# power.net
KiCad netlist of a schematic drawn in EAGLE
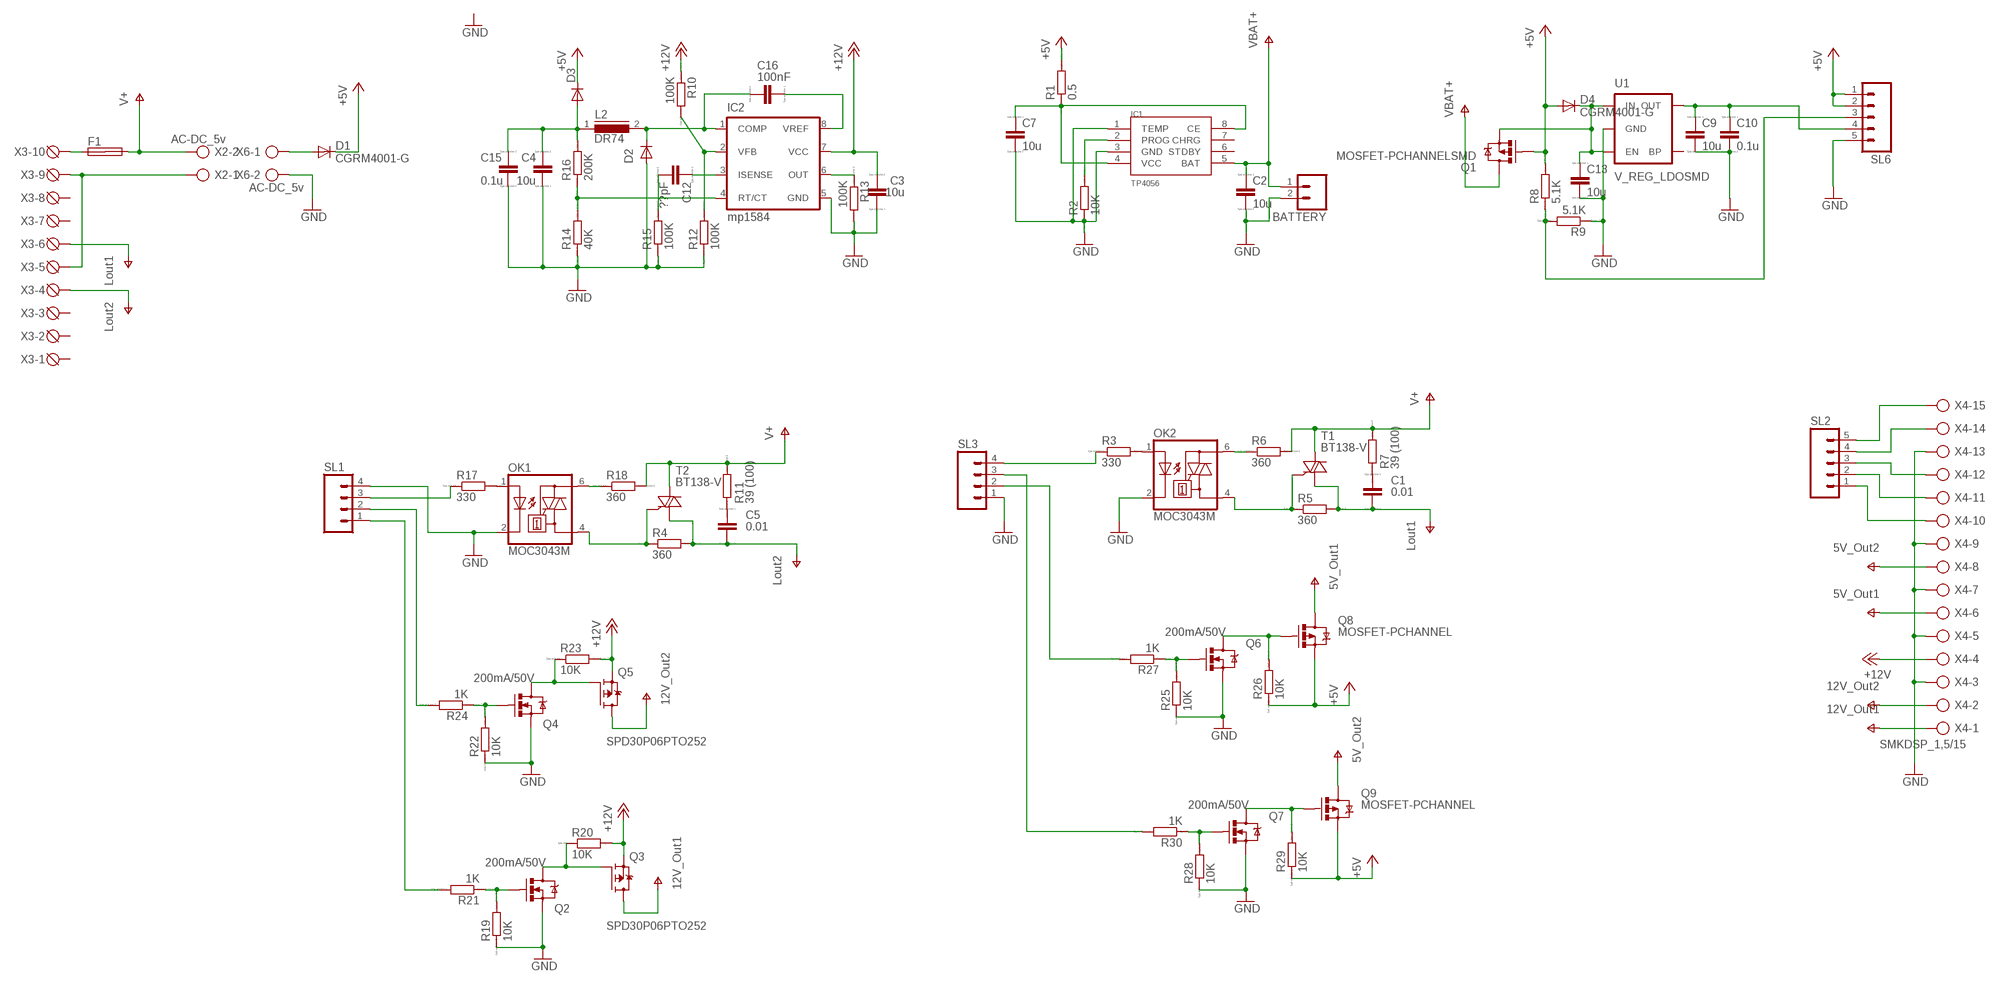
[diagram p0: schematic, sheet 1]

(export (version "E")
  (design (tool "Eeschema 10.0.6"))
  (components
    (comp (ref "BATTERY")
      (value "M02")
      (footprint "eagle-import:02P")
      (libsource (lib "eagle-import") (part "M02"))
    )
    (comp (ref "C1")
      (value "0.01")
      (footprint "eagle-import:C075-032X103")
      (libsource (lib "eagle-import") (part "C-EU075-032X103"))
    )
    (comp (ref "C2")
      (value "10u")
      (footprint "eagle-import:C0805")
      (libsource (lib "eagle-import") (part "C-EUC0805"))
    )
    (comp (ref "C3")
      (value "10u")
      (footprint "eagle-import:C1206")
      (libsource (lib "eagle-import") (part "C-EUC1206"))
    )
    (comp (ref "C4")
      (value "10u")
      (footprint "eagle-import:C1206")
      (libsource (lib "eagle-import") (part "C-EUC1206"))
    )
    (comp (ref "C5")
      (value "0.01")
      (footprint "eagle-import:C075-032X103")
      (libsource (lib "eagle-import") (part "C-EU075-032X103"))
    )
    (comp (ref "C7")
      (value "10u")
      (footprint "eagle-import:C0805")
      (libsource (lib "eagle-import") (part "C-EUC0805"))
    )
    (comp (ref "C9")
      (value "10u")
      (footprint "eagle-import:C0805")
      (libsource (lib "eagle-import") (part "C-EUC0805"))
    )
    (comp (ref "C10")
      (value "0.1u")
      (footprint "eagle-import:C0805")
      (libsource (lib "eagle-import") (part "C-EUC0805"))
    )
    (comp (ref "C12")
      (value "??pF")
      (footprint "eagle-import:C0603")
      (libsource (lib "eagle-import") (part "C-EUC0603"))
    )
    (comp (ref "C13")
      (value "10u")
      (footprint "eagle-import:C0805")
      (libsource (lib "eagle-import") (part "C-EUC0805"))
    )
    (comp (ref "C15")
      (value "0.1u")
      (footprint "eagle-import:C0805")
      (libsource (lib "eagle-import") (part "C-EUC0805"))
    )
    (comp (ref "C16")
      (value "100nF")
      (footprint "eagle-import:C0603")
      (libsource (lib "eagle-import") (part "C-EUC0603"))
    )
    (comp (ref "D1")
      (value "CGRM4001-G")
      (footprint "eagle-import:SOD-123_MINI-SMA")
      (libsource (lib "eagle-import") (part "CGRM400-G1"))
    )
    (comp (ref "D2")
      (value "ES2D")
      (footprint "eagle-import:SMB")
      (libsource (lib "eagle-import") (part "ES2D"))
    )
    (comp (ref "D3")
      (value "CGRM4001-G")
      (footprint "eagle-import:SOD-123_MINI-SMA")
      (libsource (lib "eagle-import") (part "CGRM400-G1"))
    )
    (comp (ref "D4")
      (value "CGRM4001-G")
      (footprint "eagle-import:SOD-123_MINI-SMA")
      (libsource (lib "eagle-import") (part "CGRM400-G1"))
    )
    (comp (ref "F1")
      (value "SHK20L")
      (footprint "eagle-import:SHK20L")
      (libsource (lib "eagle-import") (part "SHK20L"))
    )
    (comp (ref "IC1")
      (value "TP4056")
      (footprint "eagle-import:SOP-8")
      (libsource (lib "eagle-import") (part "TP4056"))
    )
    (comp (ref "IC2")
      (value "mp1584")
      (footprint "eagle-import:SO-08")
      (libsource (lib "eagle-import") (part "UC384D14"))
    )
    (comp (ref "L2")
      (value "DR74")
      (footprint "eagle-import:DR74")
      (libsource (lib "eagle-import") (part "DR74"))
    )
    (comp (ref "OK1")
      (value "MOC3043M")
      (footprint "eagle-import:DIL06")
      (fields (field (name "MF") "FAIRCHILD SEMICONDUCTOR") (field (name "MPN") "MOC3043-M"))
      (libsource (lib "eagle-import") (part "MOC3043M"))
    )
    (comp (ref "OK2")
      (value "MOC3043M")
      (footprint "eagle-import:DIL06")
      (fields (field (name "MF") "FAIRCHILD SEMICONDUCTOR") (field (name "MPN") "MOC3043-M"))
      (libsource (lib "eagle-import") (part "MOC3043M"))
    )
    (comp (ref "Q1")
      (value "MOSFET-PCHANNELSMD")
      (footprint "eagle-import:SOT23-3")
      (libsource (lib "eagle-import") (part "MOSFET-PCHANNELSMD"))
    )
    (comp (ref "Q2")
      (value "200mA/50V")
      (footprint "eagle-import:SOT23-3")
      (libsource (lib "eagle-import") (part "MOSFET-NCHANNELBSS138"))
    )
    (comp (ref "Q3")
      (value "SPD30P06PTO252")
      (footprint "eagle-import:TO252")
      (libsource (lib "eagle-import") (part "SPD30P06PTO252"))
    )
    (comp (ref "Q4")
      (value "200mA/50V")
      (footprint "eagle-import:SOT23-3")
      (libsource (lib "eagle-import") (part "MOSFET-NCHANNELBSS138"))
    )
    (comp (ref "Q5")
      (value "SPD30P06PTO252")
      (footprint "eagle-import:TO252")
      (libsource (lib "eagle-import") (part "SPD30P06PTO252"))
    )
    (comp (ref "Q6")
      (value "200mA/50V")
      (footprint "eagle-import:SOT23-3")
      (libsource (lib "eagle-import") (part "MOSFET-NCHANNELBSS138"))
    )
    (comp (ref "Q7")
      (value "200mA/50V")
      (footprint "eagle-import:SOT23-3")
      (libsource (lib "eagle-import") (part "MOSFET-NCHANNELBSS138"))
    )
    (comp (ref "Q8")
      (value "MOSFET-PCHANNEL")
      (footprint "eagle-import:SOT23-3")
      (libsource (lib "eagle-import") (part "MOSFET-PCHANNEL"))
    )
    (comp (ref "Q9")
      (value "MOSFET-PCHANNEL")
      (footprint "eagle-import:SOT23-3")
      (libsource (lib "eagle-import") (part "MOSFET-PCHANNEL"))
    )
    (comp (ref "R1")
      (value "0.5")
      (footprint "eagle-import:R0805")
      (libsource (lib "eagle-import") (part "R-EU_R0805"))
    )
    (comp (ref "R2")
      (value "10K")
      (footprint "eagle-import:R0805")
      (libsource (lib "eagle-import") (part "R-EU_R0805"))
    )
    (comp (ref "R3")
      (value "330")
      (footprint "eagle-import:R1206")
      (libsource (lib "eagle-import") (part "R-EU_R1206"))
    )
    (comp (ref "R4")
      (value "360")
      (footprint "eagle-import:0204_7")
      (libsource (lib "eagle-import") (part "R-EU_0204_7"))
    )
    (comp (ref "R5")
      (value "360")
      (footprint "eagle-import:0204_7")
      (libsource (lib "eagle-import") (part "R-EU_0204_7"))
    )
    (comp (ref "R6")
      (value "360")
      (footprint "eagle-import:R1206")
      (libsource (lib "eagle-import") (part "R-EU_R1206"))
    )
    (comp (ref "R7")
      (value "39 (100)")
      (footprint "eagle-import:0411_12")
      (libsource (lib "eagle-import") (part "R-EU_0411_12"))
    )
    (comp (ref "R8")
      (value "5.1K")
      (footprint "eagle-import:R0805")
      (libsource (lib "eagle-import") (part "R-EU_R0805"))
    )
    (comp (ref "R9")
      (value "5.1K")
      (footprint "eagle-import:R0805")
      (libsource (lib "eagle-import") (part "R-EU_R0805"))
    )
    (comp (ref "R10")
      (value "100K")
      (footprint "eagle-import:R0603")
      (libsource (lib "eagle-import") (part "R-EU_R0603"))
    )
    (comp (ref "R11")
      (value "39 (100)")
      (footprint "eagle-import:0411_12")
      (libsource (lib "eagle-import") (part "R-EU_0411_12"))
    )
    (comp (ref "R12")
      (value "100K")
      (footprint "eagle-import:R0603")
      (libsource (lib "eagle-import") (part "R-EU_R0603"))
    )
    (comp (ref "R13")
      (value "100K")
      (footprint "eagle-import:R0603")
      (libsource (lib "eagle-import") (part "R-EU_R0603"))
    )
    (comp (ref "R14")
      (value "40K")
      (footprint "eagle-import:R0603")
      (libsource (lib "eagle-import") (part "R-EU_R0603"))
    )
    (comp (ref "R15")
      (value "100K")
      (footprint "eagle-import:R0603")
      (libsource (lib "eagle-import") (part "R-EU_R0603"))
    )
    (comp (ref "R16")
      (value "200K")
      (footprint "eagle-import:R0603")
      (libsource (lib "eagle-import") (part "R-EU_R0603"))
    )
    (comp (ref "R17")
      (value "330")
      (footprint "eagle-import:R1206")
      (libsource (lib "eagle-import") (part "R-EU_R1206"))
    )
    (comp (ref "R18")
      (value "360")
      (footprint "eagle-import:R1206")
      (libsource (lib "eagle-import") (part "R-EU_R1206"))
    )
    (comp (ref "R19")
      (value "10K")
      (footprint "eagle-import:R0805")
      (libsource (lib "eagle-import") (part "R-EU_R0805"))
    )
    (comp (ref "R20")
      (value "10K")
      (footprint "eagle-import:R0805")
      (libsource (lib "eagle-import") (part "R-EU_R0805"))
    )
    (comp (ref "R21")
      (value "1K")
      (footprint "eagle-import:R0805")
      (libsource (lib "eagle-import") (part "R-EU_R0805"))
    )
    (comp (ref "R22")
      (value "10K")
      (footprint "eagle-import:R0805")
      (libsource (lib "eagle-import") (part "R-EU_R0805"))
    )
    (comp (ref "R23")
      (value "10K")
      (footprint "eagle-import:R0805")
      (libsource (lib "eagle-import") (part "R-EU_R0805"))
    )
    (comp (ref "R24")
      (value "1K")
      (footprint "eagle-import:R0805")
      (libsource (lib "eagle-import") (part "R-EU_R0805"))
    )
    (comp (ref "R25")
      (value "10K")
      (footprint "eagle-import:R0805")
      (libsource (lib "eagle-import") (part "R-EU_R0805"))
    )
    (comp (ref "R26")
      (value "10K")
      (footprint "eagle-import:R0805")
      (libsource (lib "eagle-import") (part "R-EU_R0805"))
    )
    (comp (ref "R27")
      (value "1K")
      (footprint "eagle-import:R0805")
      (libsource (lib "eagle-import") (part "R-EU_R0805"))
    )
    (comp (ref "R28")
      (value "10K")
      (footprint "eagle-import:R0805")
      (libsource (lib "eagle-import") (part "R-EU_R0805"))
    )
    (comp (ref "R29")
      (value "10K")
      (footprint "eagle-import:R0805")
      (libsource (lib "eagle-import") (part "R-EU_R0805"))
    )
    (comp (ref "R30")
      (value "1K")
      (footprint "eagle-import:R0805")
      (libsource (lib "eagle-import") (part "R-EU_R0805"))
    )
    (comp (ref "SL1")
      (value "M04")
      (footprint "eagle-import:04P")
      (libsource (lib "eagle-import") (part "M04"))
    )
    (comp (ref "SL2")
      (value "M05")
      (footprint "eagle-import:05P")
      (libsource (lib "eagle-import") (part "M05"))
    )
    (comp (ref "SL3")
      (value "M04")
      (footprint "eagle-import:04P")
      (libsource (lib "eagle-import") (part "M04"))
    )
    (comp (ref "SL6")
      (value "M05")
      (footprint "eagle-import:05P")
      (libsource (lib "eagle-import") (part "M05"))
    )
    (comp (ref "T1")
      (value "BT138-V")
      (footprint "eagle-import:TO220BV")
      (libsource (lib "eagle-import") (part "BT138-V"))
    )
    (comp (ref "T2")
      (value "BT138-V")
      (footprint "eagle-import:TO220BV")
      (libsource (lib "eagle-import") (part "BT138-V"))
    )
    (comp (ref "U1")
      (value "V_REG_LDOSMD")
      (footprint "eagle-import:SOT23-5")
      (libsource (lib "eagle-import") (part "V_REG_LDOSMD"))
    )
    (comp (ref "X2")
      (value "AC-DC_5v")
      (footprint "eagle-import:AK300_2")
      (libsource (lib "eagle-import") (part "AK300/2"))
    )
    (comp (ref "X3")
      (value "DG3XX-10")
      (footprint "eagle-import:DG129-7.5-10P")
      (libsource (lib "eagle-import") (part "DG3XX-10"))
    )
    (comp (ref "X4")
      (value "SMKDSP_1,5/15")
      (footprint "eagle-import:SMKDSP_1,5_15")
      (libsource (lib "eagle-import") (part "SMKDSP_1,5/15"))
    )
    (comp (ref "X6")
      (value "AC-DC_5v")
      (footprint "eagle-import:AK300_2")
      (libsource (lib "eagle-import") (part "AK300/2"))
    )
  )
  (nets
    (net (code "1") (name "+5V") (class "Default")
      (node (ref "D1") (pin "C") (pinfunction "C_C") (pintype "passive"))
      (node (ref "D3") (pin "C") (pinfunction "C_C") (pintype "passive"))
      (node (ref "D4") (pin "A") (pinfunction "A_A") (pintype "passive"))
      (node (ref "Q1") (pin "1") (pinfunction "G_1") (pintype "passive"))
      (node (ref "Q8") (pin "2") (pinfunction "S_2") (pintype "passive"))
      (node (ref "Q9") (pin "2") (pinfunction "S_2") (pintype "passive"))
      (node (ref "R1") (pin "2") (pinfunction "2_2") (pintype "passive"))
      (node (ref "R26") (pin "1") (pinfunction "1_1") (pintype "passive"))
      (node (ref "R29") (pin "1") (pinfunction "1_1") (pintype "passive"))
      (node (ref "R8") (pin "2") (pinfunction "2_2") (pintype "passive"))
      (node (ref "SL6") (pin "1") (pinfunction "1_1") (pintype "passive"))
      (node (ref "SL6") (pin "2") (pinfunction "2_2") (pintype "passive"))
    )
    (net (code "2") (name "+12V") (class "Default")
      (node (ref "C3") (pin "2") (pinfunction "2_2") (pintype "passive"))
      (node (ref "IC2") (pin "7") (pinfunction "VCC_7") (pintype "power_in"))
      (node (ref "Q3") (pin "2") (pinfunction "S_2") (pintype "passive"))
      (node (ref "Q5") (pin "2") (pinfunction "S_2") (pintype "passive"))
      (node (ref "R10") (pin "1") (pinfunction "1_1") (pintype "passive"))
      (node (ref "R20") (pin "2") (pinfunction "2_2") (pintype "passive"))
      (node (ref "R23") (pin "2") (pinfunction "2_2") (pintype "passive"))
      (node (ref "X4") (pin "4") (pinfunction "KL_4") (pintype "passive"))
    )
    (net (code "3") (name "5V_Out1") (class "Default")
      (node (ref "Q8") (pin "3") (pinfunction "D_3") (pintype "passive"))
      (node (ref "X4") (pin "6") (pinfunction "KL_6") (pintype "passive"))
    )
    (net (code "4") (name "5V_Out2") (class "Default")
      (node (ref "Q9") (pin "3") (pinfunction "D_3") (pintype "passive"))
      (node (ref "X4") (pin "8") (pinfunction "KL_8") (pintype "passive"))
    )
    (net (code "5") (name "12V_Out1") (class "Default")
      (node (ref "Q3") (pin "3") (pinfunction "D_3") (pintype "passive"))
      (node (ref "X4") (pin "1") (pinfunction "KL_1") (pintype "passive"))
    )
    (net (code "6") (name "12V_Out2") (class "Default")
      (node (ref "Q5") (pin "3") (pinfunction "D_3") (pintype "passive"))
      (node (ref "X4") (pin "2") (pinfunction "KL_2") (pintype "passive"))
    )
    (net (code "7") (name "GND") (class "Default")
      (node (ref "BATTERY") (pin "2") (pinfunction "2_2") (pintype "passive"))
      (node (ref "C10") (pin "2") (pinfunction "2_2") (pintype "passive"))
      (node (ref "C13") (pin "2") (pinfunction "2_2") (pintype "passive"))
      (node (ref "C15") (pin "2") (pinfunction "2_2") (pintype "passive"))
      (node (ref "C2") (pin "2") (pinfunction "2_2") (pintype "passive"))
      (node (ref "C3") (pin "1") (pinfunction "1_1") (pintype "passive"))
      (node (ref "C4") (pin "1") (pinfunction "1_1") (pintype "passive"))
      (node (ref "C7") (pin "2") (pinfunction "2_2") (pintype "passive"))
      (node (ref "C9") (pin "2") (pinfunction "2_2") (pintype "passive"))
      (node (ref "D2") (pin "A") (pinfunction "A_A") (pintype "passive"))
      (node (ref "IC1") (pin "1") (pinfunction "TEMP_1") (pintype "bidirectional"))
      (node (ref "IC1") (pin "3") (pinfunction "GND_3") (pintype "bidirectional"))
      (node (ref "IC2") (pin "5") (pinfunction "GND_5") (pintype "power_in"))
      (node (ref "OK1") (pin "2") (pinfunction "C_2") (pintype "passive"))
      (node (ref "OK2") (pin "2") (pinfunction "C_2") (pintype "passive"))
      (node (ref "Q2") (pin "2") (pinfunction "S_2") (pintype "passive"))
      (node (ref "Q4") (pin "2") (pinfunction "S_2") (pintype "passive"))
      (node (ref "Q6") (pin "2") (pinfunction "S_2") (pintype "passive"))
      (node (ref "Q7") (pin "2") (pinfunction "S_2") (pintype "passive"))
      (node (ref "R12") (pin "1") (pinfunction "1_1") (pintype "passive"))
      (node (ref "R13") (pin "2") (pinfunction "2_2") (pintype "passive"))
      (node (ref "R14") (pin "1") (pinfunction "1_1") (pintype "passive"))
      (node (ref "R15") (pin "1") (pinfunction "1_1") (pintype "passive"))
      (node (ref "R19") (pin "1") (pinfunction "1_1") (pintype "passive"))
      (node (ref "R2") (pin "1") (pinfunction "1_1") (pintype "passive"))
      (node (ref "R22") (pin "1") (pinfunction "1_1") (pintype "passive"))
      (node (ref "R25") (pin "1") (pinfunction "1_1") (pintype "passive"))
      (node (ref "R28") (pin "1") (pinfunction "1_1") (pintype "passive"))
      (node (ref "R9") (pin "1") (pinfunction "1_1") (pintype "passive"))
      (node (ref "SL1") (pin "4") (pinfunction "4_4") (pintype "passive"))
      (node (ref "SL3") (pin "1") (pinfunction "1_1") (pintype "passive"))
      (node (ref "SL6") (pin "5") (pinfunction "5_5") (pintype "passive"))
      (node (ref "U1") (pin "2") (pinfunction "GND_2") (pintype "input"))
      (node (ref "X4") (pin "13") (pinfunction "KL_13") (pintype "passive"))
      (node (ref "X4") (pin "3") (pinfunction "KL_3") (pintype "passive"))
      (node (ref "X4") (pin "5") (pinfunction "KL_5") (pintype "passive"))
      (node (ref "X4") (pin "7") (pinfunction "KL_7") (pintype "passive"))
      (node (ref "X4") (pin "9") (pinfunction "KL_9") (pintype "passive"))
      (node (ref "X6") (pin "2") (pinfunction "KL_2") (pintype "passive"))
    )
    (net (code "8") (name "Lout1") (class "Default")
      (node (ref "C1") (pin "2") (pinfunction "2_2") (pintype "passive"))
      (node (ref "R5") (pin "2") (pinfunction "2_2") (pintype "passive"))
      (node (ref "T1") (pin "T1") (pinfunction "A1_T1") (pintype "passive"))
      (node (ref "X3") (pin "6") (pinfunction "KL_6") (pintype "passive"))
    )
    (net (code "9") (name "Lout2") (class "Default")
      (node (ref "C5") (pin "2") (pinfunction "2_2") (pintype "passive"))
      (node (ref "R4") (pin "2") (pinfunction "2_2") (pintype "passive"))
      (node (ref "T2") (pin "T1") (pinfunction "A1_T1") (pintype "passive"))
      (node (ref "X3") (pin "4") (pinfunction "KL_4") (pintype "passive"))
    )
    (net (code "10") (name "Net-(C1-Pad1)") (class "Default")
      (node (ref "C1") (pin "1") (pinfunction "1_1") (pintype "passive"))
      (node (ref "R7") (pin "1") (pinfunction "1_1") (pintype "passive"))
    )
    (net (code "11") (name "Net-(C5-Pad1)") (class "Default")
      (node (ref "C5") (pin "1") (pinfunction "1_1") (pintype "passive"))
      (node (ref "R11") (pin "1") (pinfunction "1_1") (pintype "passive"))
    )
    (net (code "12") (name "Net-(C12-Pad2)") (class "Default")
      (node (ref "C12") (pin "2") (pinfunction "2_2") (pintype "passive"))
      (node (ref "R15") (pin "2") (pinfunction "2_2") (pintype "passive"))
    )
    (net (code "13") (name "Net-(C15-Pad1)") (class "Default")
      (node (ref "C15") (pin "1") (pinfunction "1_1") (pintype "passive"))
      (node (ref "C4") (pin "2") (pinfunction "2_2") (pintype "passive"))
      (node (ref "D3") (pin "A") (pinfunction "A_A") (pintype "passive"))
      (node (ref "L2") (pin "1") (pinfunction "1_1") (pintype "passive"))
      (node (ref "R16") (pin "2") (pinfunction "2_2") (pintype "passive"))
    )
    (net (code "14") (name "Net-(IC1-CE)") (class "Default")
      (node (ref "C7") (pin "1") (pinfunction "1_1") (pintype "passive"))
      (node (ref "IC1") (pin "4") (pinfunction "VCC_4") (pintype "bidirectional"))
      (node (ref "IC1") (pin "8") (pinfunction "CE_8") (pintype "bidirectional"))
      (node (ref "R1") (pin "1") (pinfunction "1_1") (pintype "passive"))
    )
    (net (code "15") (name "Net-(IC1-PROG)") (class "Default")
      (node (ref "IC1") (pin "2") (pinfunction "PROG_2") (pintype "bidirectional"))
      (node (ref "R2") (pin "2") (pinfunction "2_2") (pintype "passive"))
    )
    (net (code "16") (name "Net-(IC2-COMP)") (class "Default")
      (node (ref "C16") (pin "2") (pinfunction "2_2") (pintype "passive"))
      (node (ref "D2") (pin "C") (pinfunction "C_C") (pintype "passive"))
      (node (ref "IC2") (pin "1") (pinfunction "COMP_1") (pintype "passive"))
      (node (ref "L2") (pin "2") (pinfunction "2_2") (pintype "passive"))
    )
    (net (code "17") (name "Net-(IC2-ISENSE)") (class "Default")
      (node (ref "C12") (pin "1") (pinfunction "1_1") (pintype "passive"))
      (node (ref "IC2") (pin "3") (pinfunction "ISENSE_3") (pintype "input"))
    )
    (net (code "18") (name "Net-(IC2-OUT)") (class "Default")
      (node (ref "IC2") (pin "6") (pinfunction "OUT_6") (pintype "output"))
      (node (ref "R13") (pin "1") (pinfunction "1_1") (pintype "passive"))
    )
    (net (code "19") (name "Net-(IC2-RT{slash}CT)") (class "Default")
      (node (ref "IC2") (pin "4") (pinfunction "RT/CT_4") (pintype "passive"))
      (node (ref "R14") (pin "2") (pinfunction "2_2") (pintype "passive"))
      (node (ref "R16") (pin "1") (pinfunction "1_1") (pintype "passive"))
    )
    (net (code "20") (name "Net-(IC2-VFB)") (class "Default")
      (node (ref "IC2") (pin "2") (pinfunction "VFB_2") (pintype "input"))
      (node (ref "R10") (pin "2") (pinfunction "2_2") (pintype "passive"))
      (node (ref "R12") (pin "2") (pinfunction "2_2") (pintype "passive"))
    )
    (net (code "21") (name "Net-(IC2-VREF)") (class "Default")
      (node (ref "C16") (pin "1") (pinfunction "1_1") (pintype "passive"))
      (node (ref "IC2") (pin "8") (pinfunction "VREF_8") (pintype "passive"))
    )
    (net (code "22") (name "Net-(OK1-A)") (class "Default")
      (node (ref "OK1") (pin "1") (pinfunction "A_1") (pintype "passive"))
      (node (ref "R17") (pin "2") (pinfunction "2_2") (pintype "passive"))
    )
    (net (code "23") (name "Net-(OK1-A1)") (class "Default")
      (node (ref "OK1") (pin "4") (pinfunction "A1_4") (pintype "passive"))
      (node (ref "R4") (pin "1") (pinfunction "1_1") (pintype "passive"))
      (node (ref "T2") (pin "G") (pinfunction "G_G") (pintype "passive"))
    )
    (net (code "24") (name "Net-(OK1-A2)") (class "Default")
      (node (ref "OK1") (pin "6") (pinfunction "A2_6") (pintype "passive"))
      (node (ref "R18") (pin "1") (pinfunction "1_1") (pintype "passive"))
    )
    (net (code "25") (name "Net-(OK2-A)") (class "Default")
      (node (ref "OK2") (pin "1") (pinfunction "A_1") (pintype "passive"))
      (node (ref "R3") (pin "2") (pinfunction "2_2") (pintype "passive"))
    )
    (net (code "26") (name "Net-(OK2-A1)") (class "Default")
      (node (ref "OK2") (pin "4") (pinfunction "A1_4") (pintype "passive"))
      (node (ref "R5") (pin "1") (pinfunction "1_1") (pintype "passive"))
      (node (ref "T1") (pin "G") (pinfunction "G_G") (pintype "passive"))
    )
    (net (code "27") (name "Net-(OK2-A2)") (class "Default")
      (node (ref "OK2") (pin "6") (pinfunction "A2_6") (pintype "passive"))
      (node (ref "R6") (pin "1") (pinfunction "1_1") (pintype "passive"))
    )
    (net (code "28") (name "Net-(Q1-S)") (class "Default")
      (node (ref "C13") (pin "1") (pinfunction "1_1") (pintype "passive"))
      (node (ref "D4") (pin "C") (pinfunction "C_C") (pintype "passive"))
      (node (ref "Q1") (pin "2") (pinfunction "S_2") (pintype "passive"))
      (node (ref "U1") (pin "1") (pinfunction "IN_1") (pintype "input"))
      (node (ref "U1") (pin "3") (pinfunction "EN_3") (pintype "input"))
    )
    (net (code "29") (name "Net-(Q2-D)") (class "Default")
      (node (ref "Q2") (pin "3") (pinfunction "D_3") (pintype "passive"))
      (node (ref "Q3") (pin "1") (pinfunction "G_1") (pintype "passive"))
      (node (ref "R20") (pin "1") (pinfunction "1_1") (pintype "passive"))
    )
    (net (code "30") (name "Net-(Q2-G)") (class "Default")
      (node (ref "Q2") (pin "1") (pinfunction "G_1") (pintype "passive"))
      (node (ref "R19") (pin "2") (pinfunction "2_2") (pintype "passive"))
      (node (ref "R21") (pin "1") (pinfunction "1_1") (pintype "passive"))
    )
    (net (code "31") (name "Net-(Q4-D)") (class "Default")
      (node (ref "Q4") (pin "3") (pinfunction "D_3") (pintype "passive"))
      (node (ref "Q5") (pin "1") (pinfunction "G_1") (pintype "passive"))
      (node (ref "R23") (pin "1") (pinfunction "1_1") (pintype "passive"))
    )
    (net (code "32") (name "Net-(Q4-G)") (class "Default")
      (node (ref "Q4") (pin "1") (pinfunction "G_1") (pintype "passive"))
      (node (ref "R22") (pin "2") (pinfunction "2_2") (pintype "passive"))
      (node (ref "R24") (pin "1") (pinfunction "1_1") (pintype "passive"))
    )
    (net (code "33") (name "Net-(Q6-D)") (class "Default")
      (node (ref "Q6") (pin "3") (pinfunction "D_3") (pintype "passive"))
      (node (ref "Q8") (pin "1") (pinfunction "G_1") (pintype "passive"))
      (node (ref "R26") (pin "2") (pinfunction "2_2") (pintype "passive"))
    )
    (net (code "34") (name "Net-(Q6-G)") (class "Default")
      (node (ref "Q6") (pin "1") (pinfunction "G_1") (pintype "passive"))
      (node (ref "R25") (pin "2") (pinfunction "2_2") (pintype "passive"))
      (node (ref "R27") (pin "1") (pinfunction "1_1") (pintype "passive"))
    )
    (net (code "35") (name "Net-(Q7-D)") (class "Default")
      (node (ref "Q7") (pin "3") (pinfunction "D_3") (pintype "passive"))
      (node (ref "Q9") (pin "1") (pinfunction "G_1") (pintype "passive"))
      (node (ref "R29") (pin "2") (pinfunction "2_2") (pintype "passive"))
    )
    (net (code "36") (name "Net-(Q7-G)") (class "Default")
      (node (ref "Q7") (pin "1") (pinfunction "G_1") (pintype "passive"))
      (node (ref "R28") (pin "2") (pinfunction "2_2") (pintype "passive"))
      (node (ref "R30") (pin "1") (pinfunction "1_1") (pintype "passive"))
    )
    (net (code "37") (name "Net-(R3-Pad1)") (class "Default")
      (node (ref "R3") (pin "1") (pinfunction "1_1") (pintype "passive"))
      (node (ref "SL3") (pin "4") (pinfunction "4_4") (pintype "passive"))
    )
    (net (code "38") (name "Net-(R8-Pad1)") (class "Default")
      (node (ref "R8") (pin "1") (pinfunction "1_1") (pintype "passive"))
      (node (ref "R9") (pin "2") (pinfunction "2_2") (pintype "passive"))
      (node (ref "SL6") (pin "3") (pinfunction "3_3") (pintype "passive"))
    )
    (net (code "39") (name "Net-(R17-Pad1)") (class "Default")
      (node (ref "R17") (pin "1") (pinfunction "1_1") (pintype "passive"))
      (node (ref "SL1") (pin "3") (pinfunction "3_3") (pintype "passive"))
    )
    (net (code "40") (name "Net-(R21-Pad2)") (class "Default")
      (node (ref "R21") (pin "2") (pinfunction "2_2") (pintype "passive"))
      (node (ref "SL1") (pin "1") (pinfunction "1_1") (pintype "passive"))
    )
    (net (code "41") (name "Net-(R24-Pad2)") (class "Default")
      (node (ref "R24") (pin "2") (pinfunction "2_2") (pintype "passive"))
      (node (ref "SL1") (pin "2") (pinfunction "2_2") (pintype "passive"))
    )
    (net (code "42") (name "Net-(R27-Pad2)") (class "Default")
      (node (ref "R27") (pin "2") (pinfunction "2_2") (pintype "passive"))
      (node (ref "SL3") (pin "2") (pinfunction "2_2") (pintype "passive"))
    )
    (net (code "43") (name "Net-(R30-Pad2)") (class "Default")
      (node (ref "R30") (pin "2") (pinfunction "2_2") (pintype "passive"))
      (node (ref "SL3") (pin "3") (pinfunction "3_3") (pintype "passive"))
    )
    (net (code "44") (name "Net-(U1-OUT)") (class "Default")
      (node (ref "C10") (pin "1") (pinfunction "1_1") (pintype "passive"))
      (node (ref "C9") (pin "1") (pinfunction "1_1") (pintype "passive"))
      (node (ref "SL6") (pin "4") (pinfunction "4_4") (pintype "passive"))
      (node (ref "U1") (pin "5") (pinfunction "OUT_5") (pintype "passive"))
    )
    (net (code "45") (name "Net-(X2A-KL)") (class "Default")
      (node (ref "X2") (pin "1") (pinfunction "KL_1") (pintype "passive"))
      (node (ref "X3") (pin "5") (pinfunction "KL_5") (pintype "passive"))
      (node (ref "X3") (pin "9") (pinfunction "KL_9") (pintype "passive"))
    )
    (net (code "46") (name "Net-(X3B-KL)") (class "Default")
      (node (ref "F1") (pin "1A") (pinfunction "1A_1A") (pintype "passive"))
      (node (ref "X3") (pin "10") (pinfunction "KL_10") (pintype "passive"))
    )
    (net (code "47") (name "Net-(X4B-KL)") (class "Default")
      (node (ref "SL2") (pin "1") (pinfunction "1_1") (pintype "passive"))
      (node (ref "X4") (pin "10") (pinfunction "KL_10") (pintype "passive"))
    )
    (net (code "48") (name "Net-(X4C-KL)") (class "Default")
      (node (ref "SL2") (pin "2") (pinfunction "2_2") (pintype "passive"))
      (node (ref "X4") (pin "11") (pinfunction "KL_11") (pintype "passive"))
    )
    (net (code "49") (name "Net-(X4D-KL)") (class "Default")
      (node (ref "SL2") (pin "3") (pinfunction "3_3") (pintype "passive"))
      (node (ref "X4") (pin "12") (pinfunction "KL_12") (pintype "passive"))
    )
    (net (code "50") (name "Net-(X4F-KL)") (class "Default")
      (node (ref "SL2") (pin "4") (pinfunction "4_4") (pintype "passive"))
      (node (ref "X4") (pin "14") (pinfunction "KL_14") (pintype "passive"))
    )
    (net (code "51") (name "Net-(X4G-KL)") (class "Default")
      (node (ref "SL2") (pin "5") (pinfunction "5_5") (pintype "passive"))
      (node (ref "X4") (pin "15") (pinfunction "KL_15") (pintype "passive"))
    )
    (net (code "52") (name "Net-(X6A-KL)") (class "Default")
      (node (ref "D1") (pin "A") (pinfunction "A_A") (pintype "passive"))
      (node (ref "X6") (pin "1") (pinfunction "KL_1") (pintype "passive"))
    )
    (net (code "53") (name "V+") (class "Default")
      (node (ref "F1") (pin "2A") (pinfunction "2A_2A") (pintype "passive"))
      (node (ref "R11") (pin "2") (pinfunction "2_2") (pintype "passive"))
      (node (ref "R18") (pin "2") (pinfunction "2_2") (pintype "passive"))
      (node (ref "R6") (pin "2") (pinfunction "2_2") (pintype "passive"))
      (node (ref "R7") (pin "2") (pinfunction "2_2") (pintype "passive"))
      (node (ref "T1") (pin "T2") (pinfunction "A2_T2") (pintype "passive"))
      (node (ref "T2") (pin "T2") (pinfunction "A2_T2") (pintype "passive"))
      (node (ref "X2") (pin "2") (pinfunction "KL_2") (pintype "passive"))
    )
    (net (code "54") (name "VBAT+") (class "Default")
      (node (ref "BATTERY") (pin "1") (pinfunction "1_1") (pintype "passive"))
      (node (ref "C2") (pin "1") (pinfunction "1_1") (pintype "passive"))
      (node (ref "IC1") (pin "5") (pinfunction "BAT_5") (pintype "bidirectional"))
      (node (ref "Q1") (pin "3") (pinfunction "D_3") (pintype "passive"))
    )
    (net (code "55") (name "unconnected-(F1-Pad1B)") (class "Default")
      (node (ref "F1") (pin "1B") (pinfunction "1B_1B") (pintype "passive"))
    )
    (net (code "56") (name "unconnected-(F1-Pad2B)") (class "Default")
      (node (ref "F1") (pin "2B") (pinfunction "2B_2B") (pintype "passive"))
    )
    (net (code "57") (name "unconnected-(IC1-CHRG-Pad7)") (class "Default")
      (node (ref "IC1") (pin "7") (pinfunction "CHRG_7") (pintype "bidirectional"))
    )
    (net (code "58") (name "unconnected-(IC1-STDBY-Pad6)") (class "Default")
      (node (ref "IC1") (pin "6") (pinfunction "STDBY_6") (pintype "bidirectional"))
    )
    (net (code "59") (name "unconnected-(U1-BP-Pad4)") (class "Default")
      (node (ref "U1") (pin "4") (pinfunction "BP_4") (pintype "input"))
    )
    (net (code "60") (name "unconnected-(X3A-KL-Pad1)") (class "Default")
      (node (ref "X3") (pin "1") (pinfunction "KL_1") (pintype "passive"))
    )
    (net (code "61") (name "unconnected-(X3C-KL-Pad2)") (class "Default")
      (node (ref "X3") (pin "2") (pinfunction "KL_2") (pintype "passive"))
    )
    (net (code "62") (name "unconnected-(X3D-KL-Pad3)") (class "Default")
      (node (ref "X3") (pin "3") (pinfunction "KL_3") (pintype "passive"))
    )
    (net (code "63") (name "unconnected-(X3H-KL-Pad7)") (class "Default")
      (node (ref "X3") (pin "7") (pinfunction "KL_7") (pintype "passive"))
    )
    (net (code "64") (name "unconnected-(X3I-KL-Pad8)") (class "Default")
      (node (ref "X3") (pin "8") (pinfunction "KL_8") (pintype "passive"))
    )
  )
)
